# schematic.net
KiCad netlist of a schematic drawn in EAGLE
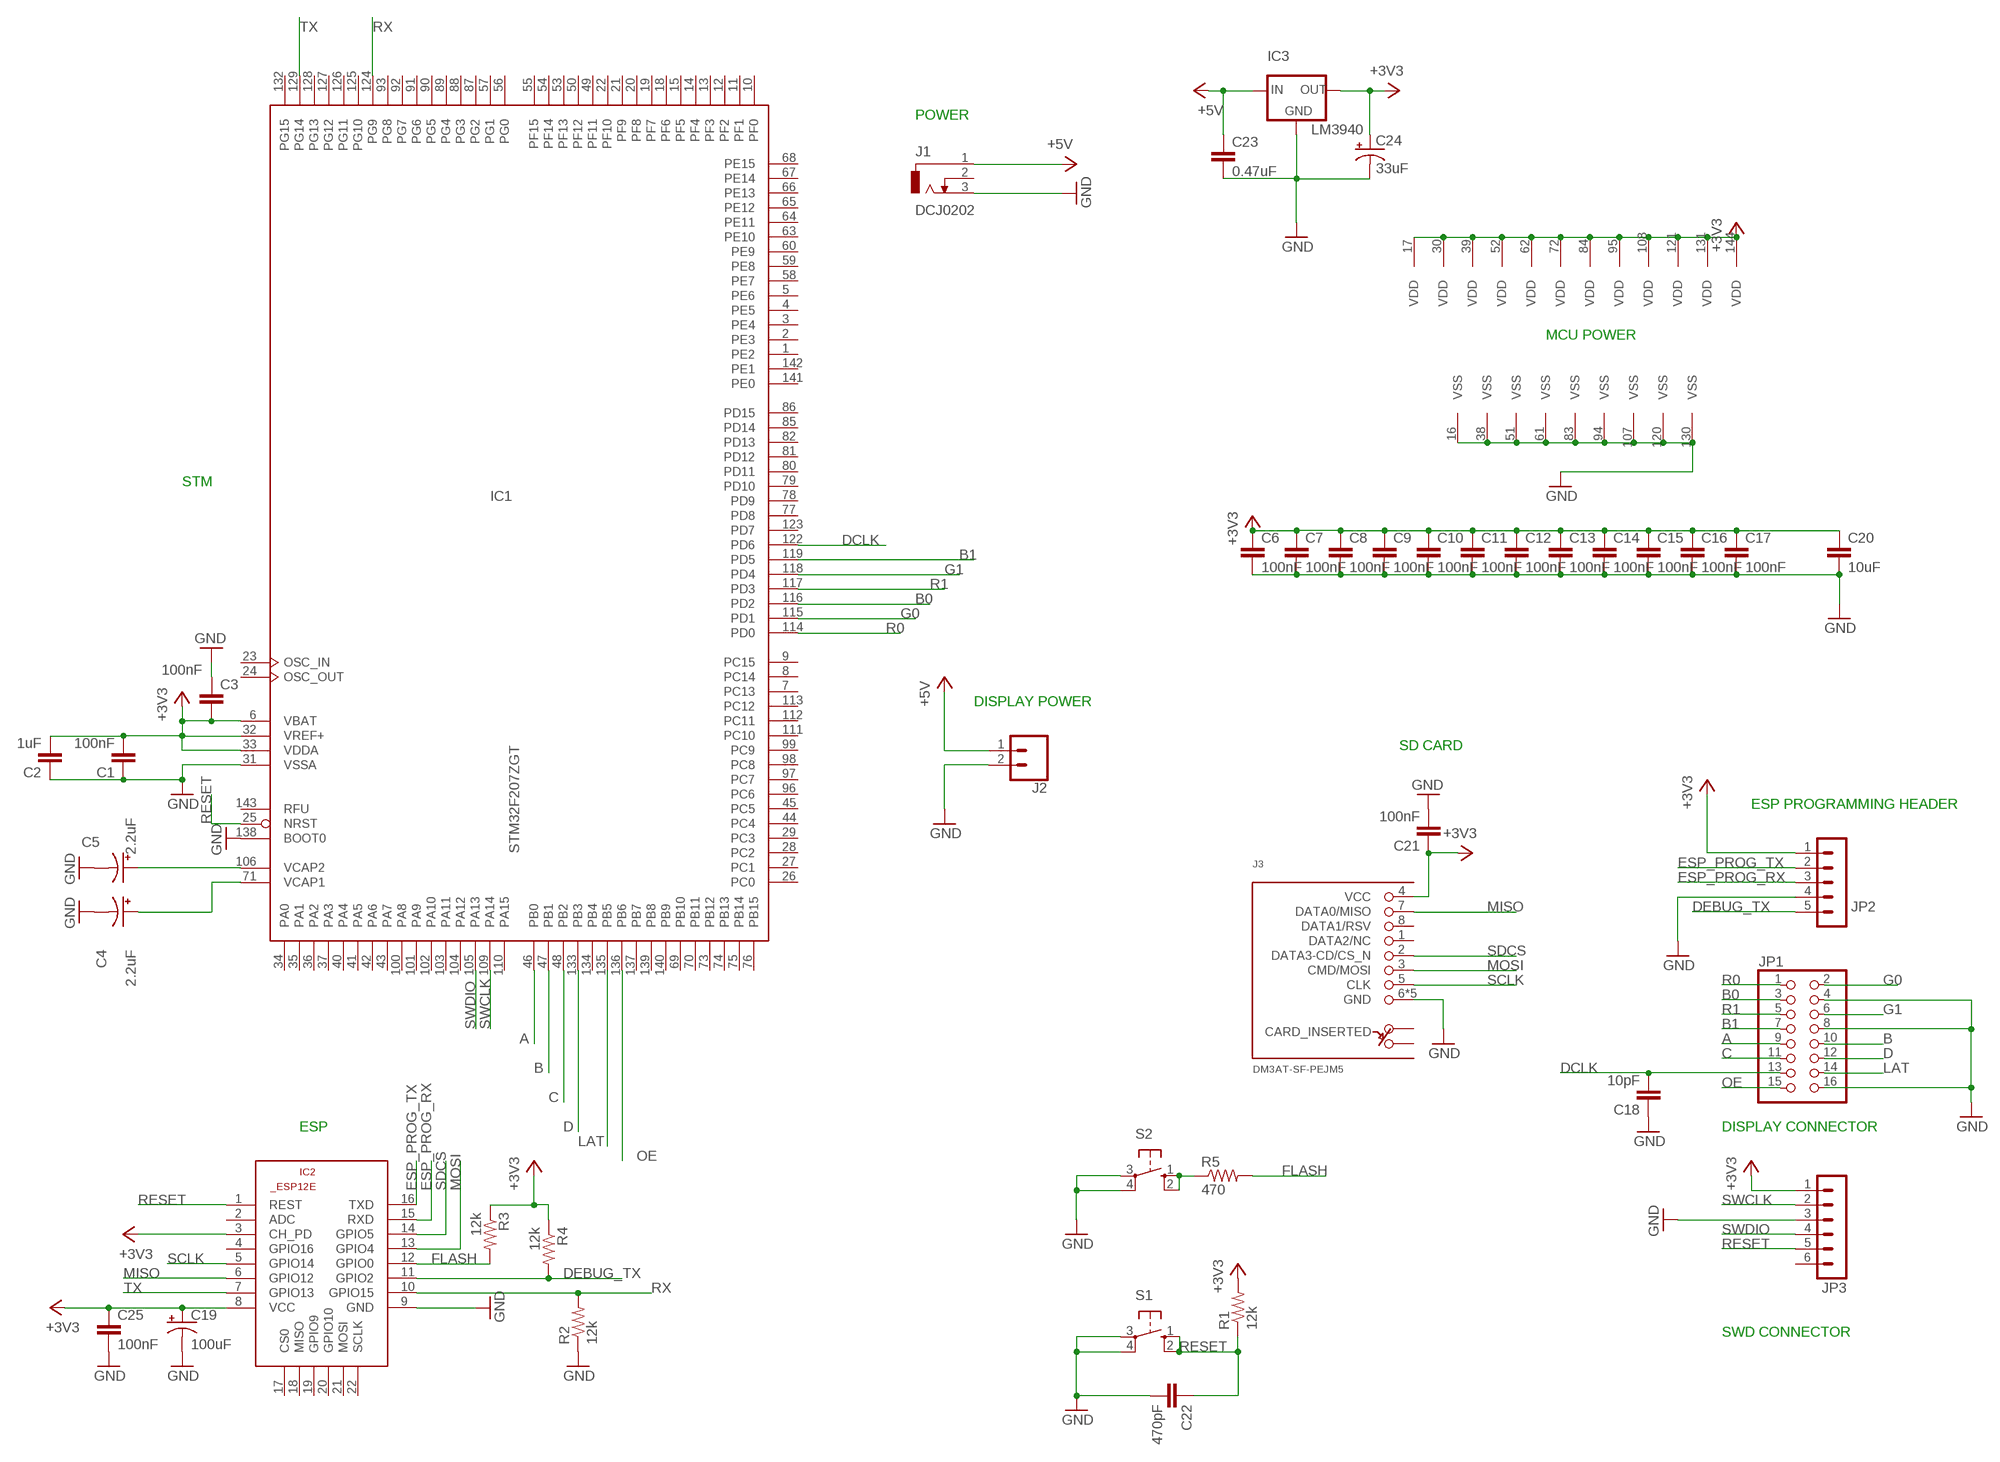
[diagram p0: schematic, sheet 1]

(export (version "E")
  (design (tool "Eeschema 10.0.6"))
  (components
    (comp (ref "C1")
      (value "100nF")
      (footprint "eagle-import:C025-025X050")
      (libsource (lib "eagle-import") (part "C-EU025-025X050"))
    )
    (comp (ref "C2")
      (value "1uF")
      (footprint "eagle-import:C050-024X044")
      (libsource (lib "eagle-import") (part "C-EU050-024X044"))
    )
    (comp (ref "C3")
      (value "100nF")
      (footprint "eagle-import:C025-025X050")
      (libsource (lib "eagle-import") (part "C-EU025-025X050"))
    )
    (comp (ref "C4")
      (value "2.2uF")
      (footprint "eagle-import:E1,8-4")
      (libsource (lib "eagle-import") (part "CPOL-USE1.8-4"))
    )
    (comp (ref "C5")
      (value "2.2uF")
      (footprint "eagle-import:E1,8-4")
      (libsource (lib "eagle-import") (part "CPOL-USE1.8-4"))
    )
    (comp (ref "C6")
      (value "100nF")
      (footprint "eagle-import:C025-025X050")
      (libsource (lib "eagle-import") (part "C-EU025-025X050"))
    )
    (comp (ref "C7")
      (value "100nF")
      (footprint "eagle-import:C025-025X050")
      (libsource (lib "eagle-import") (part "C-EU025-025X050"))
    )
    (comp (ref "C8")
      (value "100nF")
      (footprint "eagle-import:C025-025X050")
      (libsource (lib "eagle-import") (part "C-EU025-025X050"))
    )
    (comp (ref "C9")
      (value "100nF")
      (footprint "eagle-import:C025-025X050")
      (libsource (lib "eagle-import") (part "C-EU025-025X050"))
    )
    (comp (ref "C10")
      (value "100nF")
      (footprint "eagle-import:C025-025X050")
      (libsource (lib "eagle-import") (part "C-EU025-025X050"))
    )
    (comp (ref "C11")
      (value "100nF")
      (footprint "eagle-import:C025-025X050")
      (libsource (lib "eagle-import") (part "C-EU025-025X050"))
    )
    (comp (ref "C12")
      (value "100nF")
      (footprint "eagle-import:C025-025X050")
      (libsource (lib "eagle-import") (part "C-EU025-025X050"))
    )
    (comp (ref "C13")
      (value "100nF")
      (footprint "eagle-import:C025-025X050")
      (libsource (lib "eagle-import") (part "C-EU025-025X050"))
    )
    (comp (ref "C14")
      (value "100nF")
      (footprint "eagle-import:C025-025X050")
      (libsource (lib "eagle-import") (part "C-EU025-025X050"))
    )
    (comp (ref "C15")
      (value "100nF")
      (footprint "eagle-import:C025-025X050")
      (libsource (lib "eagle-import") (part "C-EU025-025X050"))
    )
    (comp (ref "C16")
      (value "100nF")
      (footprint "eagle-import:C025-025X050")
      (libsource (lib "eagle-import") (part "C-EU025-025X050"))
    )
    (comp (ref "C17")
      (value "100nF")
      (footprint "eagle-import:C025-025X050")
      (libsource (lib "eagle-import") (part "C-EU025-025X050"))
    )
    (comp (ref "C18")
      (value "10pF")
      (footprint "eagle-import:C050-024X044")
      (libsource (lib "eagle-import") (part "C-EU050-024X044"))
    )
    (comp (ref "C19")
      (value "100uF")
      (footprint "eagle-import:E2,5-6")
      (libsource (lib "eagle-import") (part "CPOL-USE2.5-6"))
    )
    (comp (ref "C20")
      (value "10uF")
      (footprint "eagle-import:C025-025X050")
      (libsource (lib "eagle-import") (part "C-EU025-025X050"))
    )
    (comp (ref "C21")
      (value "100nF")
      (footprint "eagle-import:C025-025X050")
      (libsource (lib "eagle-import") (part "C-EU025-025X050"))
    )
    (comp (ref "C22")
      (value "470pF")
      (footprint "eagle-import:C025-025X050")
      (libsource (lib "eagle-import") (part "C-EU025-025X050"))
    )
    (comp (ref "C23")
      (value "0.47uF")
      (footprint "eagle-import:C050-024X044")
      (libsource (lib "eagle-import") (part "C-EU050-024X044"))
    )
    (comp (ref "C24")
      (value "33uF")
      (footprint "eagle-import:E2-5")
      (libsource (lib "eagle-import") (part "CPOL-USE2-5"))
    )
    (comp (ref "C25")
      (value "100nF")
      (footprint "eagle-import:C025-025X050")
      (libsource (lib "eagle-import") (part "C-EU025-025X050"))
    )
    (comp (ref "IC1")
      (value "STM32F207ZGT")
      (footprint "eagle-import:LQFP144")
      (libsource (lib "eagle-import") (part "STM32F207ZTG"))
    )
    (comp (ref "IC2")
      (value "ESP8266-12EESP12E")
      (footprint "eagle-import:ESP8266-ESP12E")
      (libsource (lib "eagle-import") (part "ESP8266-12EESP12E"))
    )
    (comp (ref "IC3")
      (value "LM3940")
      (footprint "eagle-import:TO220")
      (fields (field (name "MF") "National Semiconductor"))
      (libsource (lib "eagle-import") (part "LM3940"))
    )
    (comp (ref "J1")
      (value "DCJ0202")
      (footprint "eagle-import:DCJ0202")
      (libsource (lib "eagle-import") (part "DCJ0202"))
    )
    (comp (ref "J2")
      (value "CONN_025MM")
      (footprint "eagle-import:SCREWTERMINAL-5MM-2")
      (libsource (lib "eagle-import") (part "CONN_025MM"))
    )
    (comp (ref "J3")
      (value "DM3AT-SF-PEJM5")
      (footprint "eagle-import:DM3AT-SF-PEJM5")
      (fields (field (name "MANUFACTURER") "Hirose Electric Co Ltd"))
      (libsource (lib "eagle-import") (part "DM3AT-SF-PEJM5"))
    )
    (comp (ref "JP1")
      (value "PINHD-2X8")
      (footprint "eagle-import:2X08")
      (libsource (lib "eagle-import") (part "PINHD-2X8"))
    )
    (comp (ref "JP2")
      (value "MA05-1")
      (footprint "eagle-import:MA05-1")
      (libsource (lib "eagle-import") (part "MA05-1"))
    )
    (comp (ref "JP3")
      (value "MA06-1")
      (footprint "eagle-import:MA06-1")
      (libsource (lib "eagle-import") (part "MA06-1"))
    )
    (comp (ref "R1")
      (value "12k")
      (footprint "eagle-import:0204_7")
      (libsource (lib "eagle-import") (part "R-US_0204/7"))
    )
    (comp (ref "R2")
      (value "12k")
      (footprint "eagle-import:0204_7")
      (libsource (lib "eagle-import") (part "R-US_0204/7"))
    )
    (comp (ref "R3")
      (value "12k")
      (footprint "eagle-import:0204_7")
      (libsource (lib "eagle-import") (part "R-US_0204/7"))
    )
    (comp (ref "R4")
      (value "12k")
      (footprint "eagle-import:0204_7")
      (libsource (lib "eagle-import") (part "R-US_0204/7"))
    )
    (comp (ref "R5")
      (value "470")
      (footprint "eagle-import:0204_7")
      (libsource (lib "eagle-import") (part "R-US_0204/7"))
    )
    (comp (ref "S1")
      (value "10-XX")
      (footprint "eagle-import:B3F-10XX")
      (fields (field (name "MPN") "B3F-1000"))
      (libsource (lib "eagle-import") (part "10-XX"))
    )
    (comp (ref "S2")
      (value "10-XX")
      (footprint "eagle-import:B3F-10XX")
      (fields (field (name "MPN") "B3F-1000"))
      (libsource (lib "eagle-import") (part "10-XX"))
    )
  )
  (nets
    (net (code "1") (name "+3V3") (class "Default")
      (node (ref "C1") (pin "2") (pinfunction "2_2") (pintype "passive"))
      (node (ref "C10") (pin "1") (pinfunction "1_1") (pintype "passive"))
      (node (ref "C11") (pin "1") (pinfunction "1_1") (pintype "passive"))
      (node (ref "C12") (pin "1") (pinfunction "1_1") (pintype "passive"))
      (node (ref "C13") (pin "1") (pinfunction "1_1") (pintype "passive"))
      (node (ref "C14") (pin "1") (pinfunction "1_1") (pintype "passive"))
      (node (ref "C15") (pin "1") (pinfunction "1_1") (pintype "passive"))
      (node (ref "C16") (pin "1") (pinfunction "1_1") (pintype "passive"))
      (node (ref "C17") (pin "1") (pinfunction "1_1") (pintype "passive"))
      (node (ref "C19") (pin "+") (pinfunction "+_+") (pintype "passive"))
      (node (ref "C2") (pin "2") (pinfunction "2_2") (pintype "passive"))
      (node (ref "C20") (pin "1") (pinfunction "1_1") (pintype "passive"))
      (node (ref "C21") (pin "1") (pinfunction "1_1") (pintype "passive"))
      (node (ref "C24") (pin "+") (pinfunction "+_+") (pintype "passive"))
      (node (ref "C25") (pin "1") (pinfunction "1_1") (pintype "passive"))
      (node (ref "C3") (pin "2") (pinfunction "2_2") (pintype "passive"))
      (node (ref "C6") (pin "1") (pinfunction "1_1") (pintype "passive"))
      (node (ref "C7") (pin "1") (pinfunction "1_1") (pintype "passive"))
      (node (ref "C8") (pin "1") (pinfunction "1_1") (pintype "passive"))
      (node (ref "C9") (pin "1") (pinfunction "1_1") (pintype "passive"))
      (node (ref "IC1") (pin "108") (pinfunction "VDD_108") (pintype "power_in"))
      (node (ref "IC1") (pin "121") (pinfunction "VDD_121") (pintype "power_in"))
      (node (ref "IC1") (pin "131") (pinfunction "VDD_131") (pintype "power_in"))
      (node (ref "IC1") (pin "144") (pinfunction "VDD_144") (pintype "power_in"))
      (node (ref "IC1") (pin "17") (pinfunction "VDD_17") (pintype "power_in"))
      (node (ref "IC1") (pin "30") (pinfunction "VDD_30") (pintype "power_in"))
      (node (ref "IC1") (pin "32") (pinfunction "VREF+_32") (pintype "power_in"))
      (node (ref "IC1") (pin "33") (pinfunction "VDDA_33") (pintype "power_in"))
      (node (ref "IC1") (pin "39") (pinfunction "VDD_39") (pintype "power_in"))
      (node (ref "IC1") (pin "52") (pinfunction "VDD_52") (pintype "power_in"))
      (node (ref "IC1") (pin "6") (pinfunction "VBAT_6") (pintype "power_in"))
      (node (ref "IC1") (pin "62") (pinfunction "VDD_62") (pintype "power_in"))
      (node (ref "IC1") (pin "72") (pinfunction "VDD_72") (pintype "power_in"))
      (node (ref "IC1") (pin "84") (pinfunction "VDD_84") (pintype "power_in"))
      (node (ref "IC1") (pin "95") (pinfunction "VDD_95") (pintype "power_in"))
      (node (ref "IC2") (pin "3") (pinfunction "CH_PD_3") (pintype "bidirectional"))
      (node (ref "IC2") (pin "8") (pinfunction "VCC_8") (pintype "bidirectional"))
      (node (ref "IC3") (pin "3") (pinfunction "OUT_3") (pintype "output"))
      (node (ref "J3") (pin "4") (pinfunction "VCC_4") (pintype "bidirectional"))
      (node (ref "JP2") (pin "1") (pinfunction "1_1") (pintype "passive"))
      (node (ref "JP3") (pin "1") (pinfunction "1_1") (pintype "passive"))
      (node (ref "R1") (pin "2") (pinfunction "2_2") (pintype "passive"))
      (node (ref "R3") (pin "1") (pinfunction "1_1") (pintype "passive"))
      (node (ref "R4") (pin "1") (pinfunction "1_1") (pintype "passive"))
    )
    (net (code "2") (name "+5V") (class "Default")
      (node (ref "C23") (pin "1") (pinfunction "1_1") (pintype "passive"))
      (node (ref "IC3") (pin "1") (pinfunction "IN_1") (pintype "input"))
      (node (ref "J1") (pin "1") (pinfunction "1_1") (pintype "passive"))
      (node (ref "J2") (pin "1") (pinfunction "1_1") (pintype "passive"))
    )
    (net (code "3") (name "/A") (class "Default")
      (node (ref "IC1") (pin "46") (pinfunction "PB0_46") (pintype "bidirectional"))
      (node (ref "JP1") (pin "9") (pinfunction "9_9") (pintype "passive"))
    )
    (net (code "4") (name "/B") (class "Default")
      (node (ref "IC1") (pin "47") (pinfunction "PB1_47") (pintype "bidirectional"))
      (node (ref "JP1") (pin "10") (pinfunction "10_10") (pintype "passive"))
    )
    (net (code "5") (name "/B0") (class "Default")
      (node (ref "IC1") (pin "116") (pinfunction "PD2_116") (pintype "bidirectional"))
      (node (ref "JP1") (pin "3") (pinfunction "3_3") (pintype "passive"))
    )
    (net (code "6") (name "/B1") (class "Default")
      (node (ref "IC1") (pin "119") (pinfunction "PD5_119") (pintype "bidirectional"))
      (node (ref "JP1") (pin "7") (pinfunction "7_7") (pintype "passive"))
    )
    (net (code "7") (name "/C") (class "Default")
      (node (ref "IC1") (pin "48") (pinfunction "PB2_48") (pintype "bidirectional"))
      (node (ref "JP1") (pin "11") (pinfunction "11_11") (pintype "passive"))
    )
    (net (code "8") (name "/D") (class "Default")
      (node (ref "IC1") (pin "133") (pinfunction "PB3_133") (pintype "bidirectional"))
      (node (ref "JP1") (pin "12") (pinfunction "12_12") (pintype "passive"))
    )
    (net (code "9") (name "/DCLK") (class "Default")
      (node (ref "C18") (pin "2") (pinfunction "2_2") (pintype "passive"))
      (node (ref "IC1") (pin "122") (pinfunction "PD6_122") (pintype "bidirectional"))
      (node (ref "JP1") (pin "13") (pinfunction "13_13") (pintype "passive"))
    )
    (net (code "10") (name "/DEBUG_TX") (class "Default")
      (node (ref "IC2") (pin "11") (pinfunction "GPIO2_11") (pintype "bidirectional"))
      (node (ref "JP2") (pin "5") (pinfunction "5_5") (pintype "passive"))
      (node (ref "R4") (pin "2") (pinfunction "2_2") (pintype "passive"))
    )
    (net (code "11") (name "/ESP_PROG_RX") (class "Default")
      (node (ref "IC2") (pin "15") (pinfunction "RXD_15") (pintype "bidirectional"))
      (node (ref "JP2") (pin "3") (pinfunction "3_3") (pintype "passive"))
    )
    (net (code "12") (name "/ESP_PROG_TX") (class "Default")
      (node (ref "IC2") (pin "16") (pinfunction "TXD_16") (pintype "bidirectional"))
      (node (ref "JP2") (pin "2") (pinfunction "2_2") (pintype "passive"))
    )
    (net (code "13") (name "/FLASH") (class "Default")
      (node (ref "IC2") (pin "12") (pinfunction "GPIO0_12") (pintype "bidirectional"))
      (node (ref "R3") (pin "2") (pinfunction "2_2") (pintype "passive"))
      (node (ref "R5") (pin "2") (pinfunction "2_2") (pintype "passive"))
    )
    (net (code "14") (name "/G0") (class "Default")
      (node (ref "IC1") (pin "115") (pinfunction "PD1_115") (pintype "bidirectional"))
      (node (ref "JP1") (pin "2") (pinfunction "2_2") (pintype "passive"))
    )
    (net (code "15") (name "/G1") (class "Default")
      (node (ref "IC1") (pin "118") (pinfunction "PD4_118") (pintype "bidirectional"))
      (node (ref "JP1") (pin "6") (pinfunction "6_6") (pintype "passive"))
    )
    (net (code "16") (name "/LAT") (class "Default")
      (node (ref "IC1") (pin "135") (pinfunction "PB5_135") (pintype "bidirectional"))
      (node (ref "JP1") (pin "14") (pinfunction "14_14") (pintype "passive"))
    )
    (net (code "17") (name "/MISO") (class "Default")
      (node (ref "IC2") (pin "6") (pinfunction "GPIO12_6") (pintype "bidirectional"))
      (node (ref "J3") (pin "7") (pinfunction "DATA0/MISO_7") (pintype "bidirectional"))
    )
    (net (code "18") (name "/MOSI") (class "Default")
      (node (ref "IC2") (pin "13") (pinfunction "GPIO4_13") (pintype "bidirectional"))
      (node (ref "J3") (pin "3") (pinfunction "CMD/MOSI_3") (pintype "bidirectional"))
    )
    (net (code "19") (name "/OE") (class "Default")
      (node (ref "IC1") (pin "136") (pinfunction "PB6_136") (pintype "bidirectional"))
      (node (ref "JP1") (pin "15") (pinfunction "15_15") (pintype "passive"))
    )
    (net (code "20") (name "/R0") (class "Default")
      (node (ref "IC1") (pin "114") (pinfunction "PD0_114") (pintype "bidirectional"))
      (node (ref "JP1") (pin "1") (pinfunction "1_1") (pintype "passive"))
    )
    (net (code "21") (name "/R1") (class "Default")
      (node (ref "IC1") (pin "117") (pinfunction "PD3_117") (pintype "bidirectional"))
      (node (ref "JP1") (pin "5") (pinfunction "5_5") (pintype "passive"))
    )
    (net (code "22") (name "/RESET") (class "Default")
      (node (ref "C22") (pin "1") (pinfunction "1_1") (pintype "passive"))
      (node (ref "IC1") (pin "25") (pinfunction "NRST_25") (pintype "bidirectional"))
      (node (ref "IC2") (pin "1") (pinfunction "REST_1") (pintype "bidirectional"))
      (node (ref "JP3") (pin "5") (pinfunction "5_5") (pintype "passive"))
      (node (ref "R1") (pin "1") (pinfunction "1_1") (pintype "passive"))
      (node (ref "S1") (pin "1") (pinfunction "S_1") (pintype "passive"))
      (node (ref "S1") (pin "2") (pinfunction "S1_2") (pintype "passive"))
    )
    (net (code "23") (name "/RX") (class "Default")
      (node (ref "IC1") (pin "124") (pinfunction "PG9_124") (pintype "bidirectional"))
      (node (ref "IC2") (pin "10") (pinfunction "GPIO15_10") (pintype "bidirectional"))
      (node (ref "R2") (pin "2") (pinfunction "2_2") (pintype "passive"))
    )
    (net (code "24") (name "/SCLK") (class "Default")
      (node (ref "IC2") (pin "5") (pinfunction "GPIO14_5") (pintype "bidirectional"))
      (node (ref "J3") (pin "5") (pinfunction "CLK_5") (pintype "bidirectional"))
    )
    (net (code "25") (name "/SDCS") (class "Default")
      (node (ref "IC2") (pin "14") (pinfunction "GPIO5_14") (pintype "bidirectional"))
      (node (ref "J3") (pin "2") (pinfunction "DATA3-CD/CS_N_2") (pintype "bidirectional"))
    )
    (net (code "26") (name "/SWCLK") (class "Default")
      (node (ref "IC1") (pin "109") (pinfunction "PA14_109") (pintype "bidirectional"))
      (node (ref "JP3") (pin "2") (pinfunction "2_2") (pintype "passive"))
    )
    (net (code "27") (name "/SWDIO") (class "Default")
      (node (ref "IC1") (pin "105") (pinfunction "PA13_105") (pintype "bidirectional"))
      (node (ref "JP3") (pin "4") (pinfunction "4_4") (pintype "passive"))
    )
    (net (code "28") (name "/TX") (class "Default")
      (node (ref "IC1") (pin "129") (pinfunction "PG14_129") (pintype "bidirectional"))
      (node (ref "IC2") (pin "7") (pinfunction "GPIO13_7") (pintype "bidirectional"))
    )
    (net (code "29") (name "GND") (class "Default")
      (node (ref "C1") (pin "1") (pinfunction "1_1") (pintype "passive"))
      (node (ref "C10") (pin "2") (pinfunction "2_2") (pintype "passive"))
      (node (ref "C11") (pin "2") (pinfunction "2_2") (pintype "passive"))
      (node (ref "C12") (pin "2") (pinfunction "2_2") (pintype "passive"))
      (node (ref "C13") (pin "2") (pinfunction "2_2") (pintype "passive"))
      (node (ref "C14") (pin "2") (pinfunction "2_2") (pintype "passive"))
      (node (ref "C15") (pin "2") (pinfunction "2_2") (pintype "passive"))
      (node (ref "C16") (pin "2") (pinfunction "2_2") (pintype "passive"))
      (node (ref "C17") (pin "2") (pinfunction "2_2") (pintype "passive"))
      (node (ref "C18") (pin "1") (pinfunction "1_1") (pintype "passive"))
      (node (ref "C19") (pin "-") (pinfunction "-_-") (pintype "passive"))
      (node (ref "C2") (pin "1") (pinfunction "1_1") (pintype "passive"))
      (node (ref "C20") (pin "2") (pinfunction "2_2") (pintype "passive"))
      (node (ref "C21") (pin "2") (pinfunction "2_2") (pintype "passive"))
      (node (ref "C22") (pin "2") (pinfunction "2_2") (pintype "passive"))
      (node (ref "C23") (pin "2") (pinfunction "2_2") (pintype "passive"))
      (node (ref "C24") (pin "-") (pinfunction "-_-") (pintype "passive"))
      (node (ref "C25") (pin "2") (pinfunction "2_2") (pintype "passive"))
      (node (ref "C3") (pin "1") (pinfunction "1_1") (pintype "passive"))
      (node (ref "C4") (pin "-") (pinfunction "-_-") (pintype "passive"))
      (node (ref "C5") (pin "-") (pinfunction "-_-") (pintype "passive"))
      (node (ref "C6") (pin "2") (pinfunction "2_2") (pintype "passive"))
      (node (ref "C7") (pin "2") (pinfunction "2_2") (pintype "passive"))
      (node (ref "C8") (pin "2") (pinfunction "2_2") (pintype "passive"))
      (node (ref "C9") (pin "2") (pinfunction "2_2") (pintype "passive"))
      (node (ref "IC1") (pin "107") (pinfunction "VSS_107") (pintype "power_in"))
      (node (ref "IC1") (pin "120") (pinfunction "VSS_120") (pintype "power_in"))
      (node (ref "IC1") (pin "130") (pinfunction "VSS_130") (pintype "power_in"))
      (node (ref "IC1") (pin "138") (pinfunction "BOOT0_138") (pintype "input"))
      (node (ref "IC1") (pin "16") (pinfunction "VSS_16") (pintype "power_in"))
      (node (ref "IC1") (pin "31") (pinfunction "VSSA_31") (pintype "power_in"))
      (node (ref "IC1") (pin "38") (pinfunction "VSS_38") (pintype "power_in"))
      (node (ref "IC1") (pin "51") (pinfunction "VSS_51") (pintype "power_in"))
      (node (ref "IC1") (pin "61") (pinfunction "VSS_61") (pintype "power_in"))
      (node (ref "IC1") (pin "83") (pinfunction "VSS_83") (pintype "power_in"))
      (node (ref "IC1") (pin "94") (pinfunction "VSS_94") (pintype "power_in"))
      (node (ref "IC2") (pin "9") (pinfunction "GND_9") (pintype "bidirectional"))
      (node (ref "IC3") (pin "2") (pinfunction "GND_2") (pintype "input"))
      (node (ref "J1") (pin "3") (pinfunction "3_3") (pintype "passive"))
      (node (ref "J2") (pin "2") (pinfunction "2_2") (pintype "passive"))
      (node (ref "J3") (pin "6") (pinfunction "GND_6") (pintype "bidirectional"))
      (node (ref "J3") (pin "MOUNT0") (pinfunction "GND_MOUNT0") (pintype "bidirectional"))
      (node (ref "J3") (pin "MOUNT1") (pinfunction "GND_MOUNT1") (pintype "bidirectional"))
      (node (ref "J3") (pin "MOUNT2") (pinfunction "GND_MOUNT2") (pintype "bidirectional"))
      (node (ref "J3") (pin "MOUNT3") (pinfunction "GND_MOUNT3") (pintype "bidirectional"))
      (node (ref "JP1") (pin "16") (pinfunction "16_16") (pintype "passive"))
      (node (ref "JP1") (pin "4") (pinfunction "4_4") (pintype "passive"))
      (node (ref "JP1") (pin "8") (pinfunction "8_8") (pintype "passive"))
      (node (ref "JP2") (pin "4") (pinfunction "4_4") (pintype "passive"))
      (node (ref "JP3") (pin "3") (pinfunction "3_3") (pintype "passive"))
      (node (ref "R2") (pin "1") (pinfunction "1_1") (pintype "passive"))
      (node (ref "S1") (pin "3") (pinfunction "P_3") (pintype "passive"))
      (node (ref "S1") (pin "4") (pinfunction "P1_4") (pintype "passive"))
      (node (ref "S2") (pin "3") (pinfunction "P_3") (pintype "passive"))
      (node (ref "S2") (pin "4") (pinfunction "P1_4") (pintype "passive"))
    )
    (net (code "30") (name "Net-(IC1A-VCAP1)") (class "Default")
      (node (ref "C4") (pin "+") (pinfunction "+_+") (pintype "passive"))
      (node (ref "IC1") (pin "71") (pinfunction "VCAP1_71") (pintype "power_in"))
    )
    (net (code "31") (name "Net-(IC1A-VCAP2)") (class "Default")
      (node (ref "C5") (pin "+") (pinfunction "+_+") (pintype "passive"))
      (node (ref "IC1") (pin "106") (pinfunction "VCAP2_106") (pintype "power_in"))
    )
    (net (code "32") (name "Net-(S2-S)") (class "Default")
      (node (ref "R5") (pin "1") (pinfunction "1_1") (pintype "passive"))
      (node (ref "S2") (pin "1") (pinfunction "S_1") (pintype "passive"))
      (node (ref "S2") (pin "2") (pinfunction "S1_2") (pintype "passive"))
    )
    (net (code "33") (name "unconnected-(IC1A-OSC_IN-Pad23)") (class "Default")
      (node (ref "IC1") (pin "23") (pinfunction "OSC_IN_23") (pintype "bidirectional"))
    )
    (net (code "34") (name "unconnected-(IC1A-OSC_OUT-Pad24)") (class "Default")
      (node (ref "IC1") (pin "24") (pinfunction "OSC_OUT_24") (pintype "bidirectional"))
    )
    (net (code "35") (name "unconnected-(IC1A-PA0-Pad34)") (class "Default")
      (node (ref "IC1") (pin "34") (pinfunction "PA0_34") (pintype "bidirectional"))
    )
    (net (code "36") (name "unconnected-(IC1A-PA1-Pad35)") (class "Default")
      (node (ref "IC1") (pin "35") (pinfunction "PA1_35") (pintype "bidirectional"))
    )
    (net (code "37") (name "unconnected-(IC1A-PA2-Pad36)") (class "Default")
      (node (ref "IC1") (pin "36") (pinfunction "PA2_36") (pintype "bidirectional"))
    )
    (net (code "38") (name "unconnected-(IC1A-PA3-Pad37)") (class "Default")
      (node (ref "IC1") (pin "37") (pinfunction "PA3_37") (pintype "bidirectional"))
    )
    (net (code "39") (name "unconnected-(IC1A-PA4-Pad40)") (class "Default")
      (node (ref "IC1") (pin "40") (pinfunction "PA4_40") (pintype "bidirectional"))
    )
    (net (code "40") (name "unconnected-(IC1A-PA5-Pad41)") (class "Default")
      (node (ref "IC1") (pin "41") (pinfunction "PA5_41") (pintype "bidirectional"))
    )
    (net (code "41") (name "unconnected-(IC1A-PA6-Pad42)") (class "Default")
      (node (ref "IC1") (pin "42") (pinfunction "PA6_42") (pintype "bidirectional"))
    )
    (net (code "42") (name "unconnected-(IC1A-PA7-Pad43)") (class "Default")
      (node (ref "IC1") (pin "43") (pinfunction "PA7_43") (pintype "bidirectional"))
    )
    (net (code "43") (name "unconnected-(IC1A-PA8-Pad100)") (class "Default")
      (node (ref "IC1") (pin "100") (pinfunction "PA8_100") (pintype "bidirectional"))
    )
    (net (code "44") (name "unconnected-(IC1A-PA9-Pad101)") (class "Default")
      (node (ref "IC1") (pin "101") (pinfunction "PA9_101") (pintype "bidirectional"))
    )
    (net (code "45") (name "unconnected-(IC1A-PA10-Pad102)") (class "Default")
      (node (ref "IC1") (pin "102") (pinfunction "PA10_102") (pintype "bidirectional"))
    )
    (net (code "46") (name "unconnected-(IC1A-PA11-Pad103)") (class "Default")
      (node (ref "IC1") (pin "103") (pinfunction "PA11_103") (pintype "bidirectional"))
    )
    (net (code "47") (name "unconnected-(IC1A-PA12-Pad104)") (class "Default")
      (node (ref "IC1") (pin "104") (pinfunction "PA12_104") (pintype "bidirectional"))
    )
    (net (code "48") (name "unconnected-(IC1A-PA15-Pad110)") (class "Default")
      (node (ref "IC1") (pin "110") (pinfunction "PA15_110") (pintype "bidirectional"))
    )
    (net (code "49") (name "unconnected-(IC1A-PB4-Pad134)") (class "Default")
      (node (ref "IC1") (pin "134") (pinfunction "PB4_134") (pintype "bidirectional"))
    )
    (net (code "50") (name "unconnected-(IC1A-PB7-Pad137)") (class "Default")
      (node (ref "IC1") (pin "137") (pinfunction "PB7_137") (pintype "bidirectional"))
    )
    (net (code "51") (name "unconnected-(IC1A-PB8-Pad139)") (class "Default")
      (node (ref "IC1") (pin "139") (pinfunction "PB8_139") (pintype "bidirectional"))
    )
    (net (code "52") (name "unconnected-(IC1A-PB9-Pad140)") (class "Default")
      (node (ref "IC1") (pin "140") (pinfunction "PB9_140") (pintype "bidirectional"))
    )
    (net (code "53") (name "unconnected-(IC1A-PB10-Pad69)") (class "Default")
      (node (ref "IC1") (pin "69") (pinfunction "PB10_69") (pintype "bidirectional"))
    )
    (net (code "54") (name "unconnected-(IC1A-PB11-Pad70)") (class "Default")
      (node (ref "IC1") (pin "70") (pinfunction "PB11_70") (pintype "bidirectional"))
    )
    (net (code "55") (name "unconnected-(IC1A-PB12-Pad73)") (class "Default")
      (node (ref "IC1") (pin "73") (pinfunction "PB12_73") (pintype "bidirectional"))
    )
    (net (code "56") (name "unconnected-(IC1A-PB13-Pad74)") (class "Default")
      (node (ref "IC1") (pin "74") (pinfunction "PB13_74") (pintype "bidirectional"))
    )
    (net (code "57") (name "unconnected-(IC1A-PB14-Pad75)") (class "Default")
      (node (ref "IC1") (pin "75") (pinfunction "PB14_75") (pintype "bidirectional"))
    )
    (net (code "58") (name "unconnected-(IC1A-PB15-Pad76)") (class "Default")
      (node (ref "IC1") (pin "76") (pinfunction "PB15_76") (pintype "bidirectional"))
    )
    (net (code "59") (name "unconnected-(IC1A-PC0-Pad26)") (class "Default")
      (node (ref "IC1") (pin "26") (pinfunction "PC0_26") (pintype "bidirectional"))
    )
    (net (code "60") (name "unconnected-(IC1A-PC1-Pad27)") (class "Default")
      (node (ref "IC1") (pin "27") (pinfunction "PC1_27") (pintype "bidirectional"))
    )
    (net (code "61") (name "unconnected-(IC1A-PC2-Pad28)") (class "Default")
      (node (ref "IC1") (pin "28") (pinfunction "PC2_28") (pintype "bidirectional"))
    )
    (net (code "62") (name "unconnected-(IC1A-PC3-Pad29)") (class "Default")
      (node (ref "IC1") (pin "29") (pinfunction "PC3_29") (pintype "bidirectional"))
    )
    (net (code "63") (name "unconnected-(IC1A-PC4-Pad44)") (class "Default")
      (node (ref "IC1") (pin "44") (pinfunction "PC4_44") (pintype "bidirectional"))
    )
    (net (code "64") (name "unconnected-(IC1A-PC5-Pad45)") (class "Default")
      (node (ref "IC1") (pin "45") (pinfunction "PC5_45") (pintype "bidirectional"))
    )
    (net (code "65") (name "unconnected-(IC1A-PC6-Pad96)") (class "Default")
      (node (ref "IC1") (pin "96") (pinfunction "PC6_96") (pintype "bidirectional"))
    )
    (net (code "66") (name "unconnected-(IC1A-PC7-Pad97)") (class "Default")
      (node (ref "IC1") (pin "97") (pinfunction "PC7_97") (pintype "bidirectional"))
    )
    (net (code "67") (name "unconnected-(IC1A-PC8-Pad98)") (class "Default")
      (node (ref "IC1") (pin "98") (pinfunction "PC8_98") (pintype "bidirectional"))
    )
    (net (code "68") (name "unconnected-(IC1A-PC9-Pad99)") (class "Default")
      (node (ref "IC1") (pin "99") (pinfunction "PC9_99") (pintype "bidirectional"))
    )
    (net (code "69") (name "unconnected-(IC1A-PC10-Pad111)") (class "Default")
      (node (ref "IC1") (pin "111") (pinfunction "PC10_111") (pintype "bidirectional"))
    )
    (net (code "70") (name "unconnected-(IC1A-PC11-Pad112)") (class "Default")
      (node (ref "IC1") (pin "112") (pinfunction "PC11_112") (pintype "bidirectional"))
    )
    (net (code "71") (name "unconnected-(IC1A-PC12-Pad113)") (class "Default")
      (node (ref "IC1") (pin "113") (pinfunction "PC12_113") (pintype "bidirectional"))
    )
    (net (code "72") (name "unconnected-(IC1A-PC13-Pad7)") (class "Default")
      (node (ref "IC1") (pin "7") (pinfunction "PC13_7") (pintype "bidirectional"))
    )
    (net (code "73") (name "unconnected-(IC1A-PC14-Pad8)") (class "Default")
      (node (ref "IC1") (pin "8") (pinfunction "PC14_8") (pintype "bidirectional"))
    )
    (net (code "74") (name "unconnected-(IC1A-PC15-Pad9)") (class "Default")
      (node (ref "IC1") (pin "9") (pinfunction "PC15_9") (pintype "bidirectional"))
    )
    (net (code "75") (name "unconnected-(IC1A-PD7-Pad123)") (class "Default")
      (node (ref "IC1") (pin "123") (pinfunction "PD7_123") (pintype "bidirectional"))
    )
    (net (code "76") (name "unconnected-(IC1A-PD8-Pad77)") (class "Default")
      (node (ref "IC1") (pin "77") (pinfunction "PD8_77") (pintype "bidirectional"))
    )
    (net (code "77") (name "unconnected-(IC1A-PD9-Pad78)") (class "Default")
      (node (ref "IC1") (pin "78") (pinfunction "PD9_78") (pintype "bidirectional"))
    )
    (net (code "78") (name "unconnected-(IC1A-PD10-Pad79)") (class "Default")
      (node (ref "IC1") (pin "79") (pinfunction "PD10_79") (pintype "bidirectional"))
    )
    (net (code "79") (name "unconnected-(IC1A-PD11-Pad80)") (class "Default")
      (node (ref "IC1") (pin "80") (pinfunction "PD11_80") (pintype "bidirectional"))
    )
    (net (code "80") (name "unconnected-(IC1A-PD12-Pad81)") (class "Default")
      (node (ref "IC1") (pin "81") (pinfunction "PD12_81") (pintype "bidirectional"))
    )
    (net (code "81") (name "unconnected-(IC1A-PD13-Pad82)") (class "Default")
      (node (ref "IC1") (pin "82") (pinfunction "PD13_82") (pintype "bidirectional"))
    )
    (net (code "82") (name "unconnected-(IC1A-PD14-Pad85)") (class "Default")
      (node (ref "IC1") (pin "85") (pinfunction "PD14_85") (pintype "bidirectional"))
    )
    (net (code "83") (name "unconnected-(IC1A-PD15-Pad86)") (class "Default")
      (node (ref "IC1") (pin "86") (pinfunction "PD15_86") (pintype "bidirectional"))
    )
    (net (code "84") (name "unconnected-(IC1A-PE0-Pad141)") (class "Default")
      (node (ref "IC1") (pin "141") (pinfunction "PE0_141") (pintype "bidirectional"))
    )
    (net (code "85") (name "unconnected-(IC1A-PE1-Pad142)") (class "Default")
      (node (ref "IC1") (pin "142") (pinfunction "PE1_142") (pintype "bidirectional"))
    )
    (net (code "86") (name "unconnected-(IC1A-PE2-Pad1)") (class "Default")
      (node (ref "IC1") (pin "1") (pinfunction "PE2_1") (pintype "bidirectional"))
    )
    (net (code "87") (name "unconnected-(IC1A-PE3-Pad2)") (class "Default")
      (node (ref "IC1") (pin "2") (pinfunction "PE3_2") (pintype "bidirectional"))
    )
    (net (code "88") (name "unconnected-(IC1A-PE4-Pad3)") (class "Default")
      (node (ref "IC1") (pin "3") (pinfunction "PE4_3") (pintype "bidirectional"))
    )
    (net (code "89") (name "unconnected-(IC1A-PE5-Pad4)") (class "Default")
      (node (ref "IC1") (pin "4") (pinfunction "PE5_4") (pintype "bidirectional"))
    )
    (net (code "90") (name "unconnected-(IC1A-PE6-Pad5)") (class "Default")
      (node (ref "IC1") (pin "5") (pinfunction "PE6_5") (pintype "bidirectional"))
    )
    (net (code "91") (name "unconnected-(IC1A-PE7-Pad58)") (class "Default")
      (node (ref "IC1") (pin "58") (pinfunction "PE7_58") (pintype "bidirectional"))
    )
    (net (code "92") (name "unconnected-(IC1A-PE8-Pad59)") (class "Default")
      (node (ref "IC1") (pin "59") (pinfunction "PE8_59") (pintype "bidirectional"))
    )
    (net (code "93") (name "unconnected-(IC1A-PE9-Pad60)") (class "Default")
      (node (ref "IC1") (pin "60") (pinfunction "PE9_60") (pintype "bidirectional"))
    )
    (net (code "94") (name "unconnected-(IC1A-PE10-Pad63)") (class "Default")
      (node (ref "IC1") (pin "63") (pinfunction "PE10_63") (pintype "bidirectional"))
    )
    (net (code "95") (name "unconnected-(IC1A-PE11-Pad64)") (class "Default")
      (node (ref "IC1") (pin "64") (pinfunction "PE11_64") (pintype "bidirectional"))
    )
    (net (code "96") (name "unconnected-(IC1A-PE12-Pad65)") (class "Default")
      (node (ref "IC1") (pin "65") (pinfunction "PE12_65") (pintype "bidirectional"))
    )
    (net (code "97") (name "unconnected-(IC1A-PE13-Pad66)") (class "Default")
      (node (ref "IC1") (pin "66") (pinfunction "PE13_66") (pintype "bidirectional"))
    )
    (net (code "98") (name "unconnected-(IC1A-PE14-Pad67)") (class "Default")
      (node (ref "IC1") (pin "67") (pinfunction "PE14_67") (pintype "bidirectional"))
    )
    (net (code "99") (name "unconnected-(IC1A-PE15-Pad68)") (class "Default")
      (node (ref "IC1") (pin "68") (pinfunction "PE15_68") (pintype "bidirectional"))
    )
    (net (code "100") (name "unconnected-(IC1A-PF0-Pad10)") (class "Default")
      (node (ref "IC1") (pin "10") (pinfunction "PF0_10") (pintype "bidirectional"))
    )
    (net (code "101") (name "unconnected-(IC1A-PF1-Pad11)") (class "Default")
      (node (ref "IC1") (pin "11") (pinfunction "PF1_11") (pintype "bidirectional"))
    )
    (net (code "102") (name "unconnected-(IC1A-PF2-Pad12)") (class "Default")
      (node (ref "IC1") (pin "12") (pinfunction "PF2_12") (pintype "bidirectional"))
    )
    (net (code "103") (name "unconnected-(IC1A-PF3-Pad13)") (class "Default")
      (node (ref "IC1") (pin "13") (pinfunction "PF3_13") (pintype "bidirectional"))
    )
    (net (code "104") (name "unconnected-(IC1A-PF4-Pad14)") (class "Default")
      (node (ref "IC1") (pin "14") (pinfunction "PF4_14") (pintype "bidirectional"))
    )
    (net (code "105") (name "unconnected-(IC1A-PF5-Pad15)") (class "Default")
      (node (ref "IC1") (pin "15") (pinfunction "PF5_15") (pintype "bidirectional"))
    )
    (net (code "106") (name "unconnected-(IC1A-PF6-Pad18)") (class "Default")
      (node (ref "IC1") (pin "18") (pinfunction "PF6_18") (pintype "bidirectional"))
    )
    (net (code "107") (name "unconnected-(IC1A-PF7-Pad19)") (class "Default")
      (node (ref "IC1") (pin "19") (pinfunction "PF7_19") (pintype "bidirectional"))
    )
    (net (code "108") (name "unconnected-(IC1A-PF8-Pad20)") (class "Default")
      (node (ref "IC1") (pin "20") (pinfunction "PF8_20") (pintype "bidirectional"))
    )
    (net (code "109") (name "unconnected-(IC1A-PF9-Pad21)") (class "Default")
      (node (ref "IC1") (pin "21") (pinfunction "PF9_21") (pintype "bidirectional"))
    )
    (net (code "110") (name "unconnected-(IC1A-PF10-Pad22)") (class "Default")
      (node (ref "IC1") (pin "22") (pinfunction "PF10_22") (pintype "bidirectional"))
    )
    (net (code "111") (name "unconnected-(IC1A-PF11-Pad49)") (class "Default")
      (node (ref "IC1") (pin "49") (pinfunction "PF11_49") (pintype "bidirectional"))
    )
    (net (code "112") (name "unconnected-(IC1A-PF12-Pad50)") (class "Default")
      (node (ref "IC1") (pin "50") (pinfunction "PF12_50") (pintype "bidirectional"))
    )
    (net (code "113") (name "unconnected-(IC1A-PF13-Pad53)") (class "Default")
      (node (ref "IC1") (pin "53") (pinfunction "PF13_53") (pintype "bidirectional"))
    )
    (net (code "114") (name "unconnected-(IC1A-PF14-Pad54)") (class "Default")
      (node (ref "IC1") (pin "54") (pinfunction "PF14_54") (pintype "bidirectional"))
    )
    (net (code "115") (name "unconnected-(IC1A-PF15-Pad55)") (class "Default")
      (node (ref "IC1") (pin "55") (pinfunction "PF15_55") (pintype "bidirectional"))
    )
    (net (code "116") (name "unconnected-(IC1A-PG0-Pad56)") (class "Default")
      (node (ref "IC1") (pin "56") (pinfunction "PG0_56") (pintype "bidirectional"))
    )
    (net (code "117") (name "unconnected-(IC1A-PG1-Pad57)") (class "Default")
      (node (ref "IC1") (pin "57") (pinfunction "PG1_57") (pintype "bidirectional"))
    )
    (net (code "118") (name "unconnected-(IC1A-PG2-Pad87)") (class "Default")
      (node (ref "IC1") (pin "87") (pinfunction "PG2_87") (pintype "bidirectional"))
    )
    (net (code "119") (name "unconnected-(IC1A-PG3-Pad88)") (class "Default")
      (node (ref "IC1") (pin "88") (pinfunction "PG3_88") (pintype "bidirectional"))
    )
    (net (code "120") (name "unconnected-(IC1A-PG4-Pad89)") (class "Default")
      (node (ref "IC1") (pin "89") (pinfunction "PG4_89") (pintype "bidirectional"))
    )
    (net (code "121") (name "unconnected-(IC1A-PG5-Pad90)") (class "Default")
      (node (ref "IC1") (pin "90") (pinfunction "PG5_90") (pintype "bidirectional"))
    )
    (net (code "122") (name "unconnected-(IC1A-PG6-Pad91)") (class "Default")
      (node (ref "IC1") (pin "91") (pinfunction "PG6_91") (pintype "bidirectional"))
    )
    (net (code "123") (name "unconnected-(IC1A-PG7-Pad92)") (class "Default")
      (node (ref "IC1") (pin "92") (pinfunction "PG7_92") (pintype "bidirectional"))
    )
    (net (code "124") (name "unconnected-(IC1A-PG8-Pad93)") (class "Default")
      (node (ref "IC1") (pin "93") (pinfunction "PG8_93") (pintype "bidirectional"))
    )
    (net (code "125") (name "unconnected-(IC1A-PG10-Pad125)") (class "Default")
      (node (ref "IC1") (pin "125") (pinfunction "PG10_125") (pintype "bidirectional"))
    )
    (net (code "126") (name "unconnected-(IC1A-PG11-Pad126)") (class "Default")
      (node (ref "IC1") (pin "126") (pinfunction "PG11_126") (pintype "bidirectional"))
    )
    (net (code "127") (name "unconnected-(IC1A-PG12-Pad127)") (class "Default")
      (node (ref "IC1") (pin "127") (pinfunction "PG12_127") (pintype "bidirectional"))
    )
    (net (code "128") (name "unconnected-(IC1A-PG13-Pad128)") (class "Default")
      (node (ref "IC1") (pin "128") (pinfunction "PG13_128") (pintype "bidirectional"))
    )
    (net (code "129") (name "unconnected-(IC1A-PG15-Pad132)") (class "Default")
      (node (ref "IC1") (pin "132") (pinfunction "PG15_132") (pintype "bidirectional"))
    )
    (net (code "130") (name "unconnected-(IC1A-RFU-Pad143)") (class "Default")
      (node (ref "IC1") (pin "143") (pinfunction "RFU_143") (pintype "input"))
    )
    (net (code "131") (name "unconnected-(IC2-ADC-Pad2)") (class "Default")
      (node (ref "IC2") (pin "2") (pinfunction "ADC_2") (pintype "bidirectional"))
    )
    (net (code "132") (name "unconnected-(IC2-CS0-Pad17)") (class "Default")
      (node (ref "IC2") (pin "17") (pinfunction "CS0_17") (pintype "bidirectional"))
    )
    (net (code "133") (name "unconnected-(IC2-GPIO9-Pad19)") (class "Default")
      (node (ref "IC2") (pin "19") (pinfunction "GPIO9_19") (pintype "bidirectional"))
    )
    (net (code "134") (name "unconnected-(IC2-GPIO10-Pad20)") (class "Default")
      (node (ref "IC2") (pin "20") (pinfunction "GPIO10_20") (pintype "bidirectional"))
    )
    (net (code "135") (name "unconnected-(IC2-GPIO16-Pad4)") (class "Default")
      (node (ref "IC2") (pin "4") (pinfunction "GPIO16_4") (pintype "bidirectional"))
    )
    (net (code "136") (name "unconnected-(IC2-MISO-Pad18)") (class "Default")
      (node (ref "IC2") (pin "18") (pinfunction "MISO_18") (pintype "bidirectional"))
    )
    (net (code "137") (name "unconnected-(IC2-MOSI-Pad21)") (class "Default")
      (node (ref "IC2") (pin "21") (pinfunction "MOSI_21") (pintype "bidirectional"))
    )
    (net (code "138") (name "unconnected-(IC2-SCLK-Pad22)") (class "Default")
      (node (ref "IC2") (pin "22") (pinfunction "SCLK_22") (pintype "bidirectional"))
    )
    (net (code "139") (name "unconnected-(J1-Pad2)") (class "Default")
      (node (ref "J1") (pin "2") (pinfunction "2_2") (pintype "passive"))
    )
    (net (code "140") (name "unconnected-(J3-DATA1{slash}RSV-Pad8)") (class "Default")
      (node (ref "J3") (pin "8") (pinfunction "DATA1/RSV_8") (pintype "bidirectional"))
    )
    (net (code "141") (name "unconnected-(J3-DATA2{slash}NC-Pad1)") (class "Default")
      (node (ref "J3") (pin "1") (pinfunction "DATA2/NC_1") (pintype "bidirectional"))
    )
    (net (code "142") (name "unconnected-(J3-PadA)") (class "Default")
      (node (ref "J3") (pin "A") (pinfunction "A_A") (pintype "bidirectional"))
    )
    (net (code "143") (name "unconnected-(J3-PadB)") (class "Default")
      (node (ref "J3") (pin "B") (pinfunction "B_B") (pintype "bidirectional"))
    )
    (net (code "144") (name "unconnected-(JP3-Pad6)") (class "Default")
      (node (ref "JP3") (pin "6") (pinfunction "6_6") (pintype "passive"))
    )
  )
)
